# 7_-ADC_Chip.net
KiCad netlist of a schematic drawn in Altium Designer
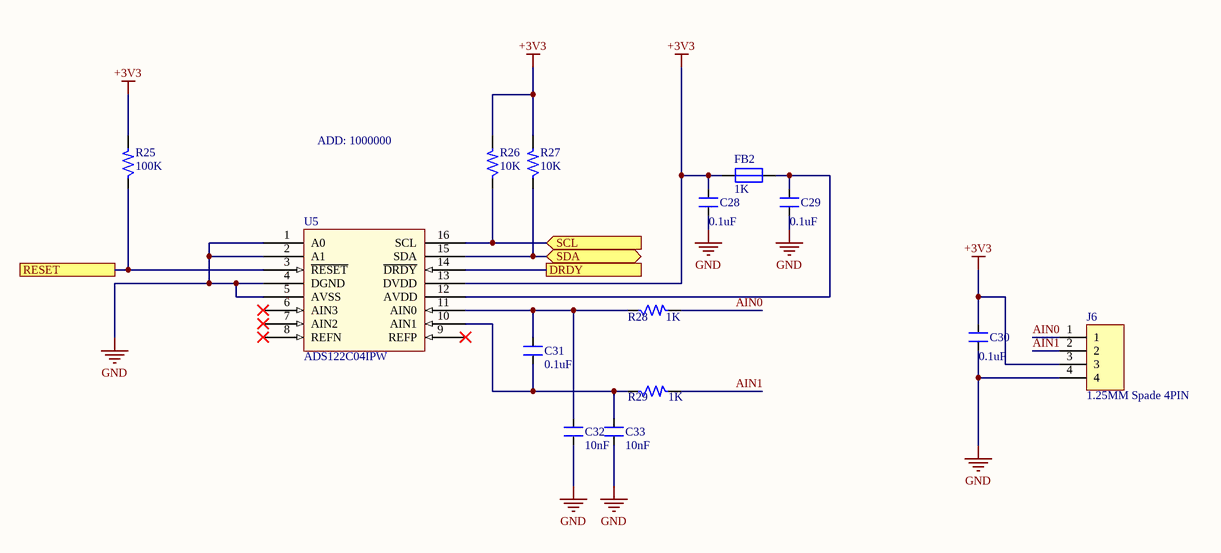
[diagram p0: [7]-ADC Chip.SchDoc]

(export (version "E")
  (design (tool "Eeschema 10.0.6"))
  (components
    (comp (ref "C28")
      (value "0.1uF")
      (footprint "CAP_0805")
      (description "0.1µF ±10% 50V Ceramic Capacitor X7R 0805 (2012 Metric)")
      (fields
        (field (name "MANUFACTURER") "Samsung")
        (field (name "MANUFACTURER PART NUMBER") "CL21B104KBCNNNC")
      )
      (libsource (lib "ESTEEMPCBLIB") (part "CAP_0.1uF-50V-10%-0805"))
    )
    (comp (ref "C29")
      (value "0.1uF")
      (footprint "CAP_0805")
      (description "0.1µF ±10% 50V Ceramic Capacitor X7R 0805 (2012 Metric)")
      (fields
        (field (name "MANUFACTURER") "Samsung")
        (field (name "MANUFACTURER PART NUMBER") "CL21B104KBCNNNC")
      )
      (libsource (lib "ESTEEMPCBLIB") (part "CAP_0.1uF-50V-10%-0805"))
    )
    (comp (ref "C30")
      (value "0.1uF")
      (footprint "CAP_0805")
      (description "0.1µF ±10% 50V Ceramic Capacitor X7R 0805 (2012 Metric)")
      (fields
        (field (name "MANUFACTURER") "Samsung")
        (field (name "MANUFACTURER PART NUMBER") "CL21B104KBCNNNC")
      )
      (libsource (lib "ESTEEMPCBLIB") (part "CAP_0.1uF-50V-10%-0805"))
    )
    (comp (ref "C31")
      (value "0.1uF")
      (footprint "CAP_0805")
      (description "0.1µF ±10% 50V Ceramic Capacitor X7R 0805 (2012 Metric)")
      (fields
        (field (name "MANUFACTURER") "Samsung")
        (field (name "MANUFACTURER PART NUMBER") "CL21B104KBCNNNC")
      )
      (libsource (lib "ESTEEMPCBLIB") (part "CAP_0.1uF-50V-10%-0805"))
    )
    (comp (ref "C32")
      (value "10nF")
      (footprint "CAP_0805")
      (description "10000pF ±10% 50V Ceramic Capacitor X7R 0805 (2012 Metric)")
      (fields
        (field (name "MANUFACTURER") "Samsung")
        (field (name "MANUFACTURER PART NUMBER") "C0805C103K5RECAUTO")
      )
      (libsource (lib "ESTEEMPCBLIB") (part "CAP_10nF-50V-10%-0805"))
    )
    (comp (ref "C33")
      (value "10nF")
      (footprint "CAP_0805")
      (description "10000pF ±10% 50V Ceramic Capacitor X7R 0805 (2012 Metric)")
      (fields
        (field (name "MANUFACTURER") "Samsung")
        (field (name "MANUFACTURER PART NUMBER") "C0805C103K5RECAUTO")
      )
      (libsource (lib "ESTEEMPCBLIB") (part "CAP_10nF-50V-10%-0805"))
    )
    (comp (ref "FB2")
      (value "1K")
      (footprint "IND_0805")
      (description "1 kOhms @ 100MHz 1 Power Line Ferrite Bead 0805 (2012 Metric) 1.6A")
      (fields
        (field (name "MANUFACTURER") "Laird")
        (field (name "MANUFACTURER PART NUMBER") "BLM21SP102SH1D")
      )
      (libsource (lib "ESTEEMPCBLIB") (part "FB_1K-100MHZ-1.6A-0805"))
    )
    (comp (ref "J6")
      (value "1.25MM Spade 4PIN")
      (footprint "CON4_50_653004117322_TH_RA")
      (description "4 Pins, 1 Row 1.25mm Pitch, right angle Connector, male")
      (fields (field (name "MANUFACTURER PART NUMBER") "653004117322") (field (name "MANUFACTURER") "JST"))
      (libsource (lib "ESTEEMPCBLIB") (part "CON-PLG_4X1-50-RA-TH"))
    )
    (comp (ref "R25")
      (value "100K")
      (footprint "RES_0603")
      (description "100 kOhms ±1% 0.1W, 1/10W Chip Resistor 0603 (1608 Metric) Automotive AEC-Q200 Thick Film")
      (fields
        (field (name "MANUFACTURER") "Stackpole Electronics")
        (field (name "MANUFACTURER PART NUMBER") "RMCF0603FT100K")
      )
      (libsource (lib "ESTEEMPCBLIB") (part "RES_100K-0.1W-1%-0603"))
    )
    (comp (ref "R26")
      (value "10K")
      (footprint "RES_0603")
      (description "10 kOhms ±1% 0.1W, 1/10W Chip Resistor 0603 (1608 Metric) Automotive AEC-Q200 Thick Film")
      (fields (field (name "MANUFACTURER") "Walsin") (field (name "MANUFACTURER PART NUMBER") "WR06X1002FTL"))
      (libsource (lib "ESTEEMPCBLIB") (part "RES_10K-0.1W-1%-0603"))
    )
    (comp (ref "R27")
      (value "10K")
      (footprint "RES_0603")
      (description "10 kOhms ±1% 0.1W, 1/10W Chip Resistor 0603 (1608 Metric) Automotive AEC-Q200 Thick Film")
      (fields (field (name "MANUFACTURER") "Walsin") (field (name "MANUFACTURER PART NUMBER") "WR06X1002FTL"))
      (libsource (lib "ESTEEMPCBLIB") (part "RES_10K-0.1W-1%-0603"))
    )
    (comp (ref "R28")
      (value "1K")
      (footprint "RES_0603")
      (description "1 kOhms ±1% 0.1W, 1/10W Chip Resistor 0603 (1608 Metric) Automotive AEC-Q200 Thick Film")
      (fields (field (name "MANUFACTURER") "Walsin") (field (name "MANUFACTURER PART NUMBER") "WR06X1001FTL"))
      (libsource (lib "ESTEEMPCBLIB") (part "RES_1K-0.1W-1%-0603"))
    )
    (comp (ref "R29")
      (value "1K")
      (footprint "RES_0603")
      (description "1 kOhms ±1% 0.1W, 1/10W Chip Resistor 0603 (1608 Metric) Automotive AEC-Q200 Thick Film")
      (fields (field (name "MANUFACTURER") "Walsin") (field (name "MANUFACTURER PART NUMBER") "WR06X1001FTL"))
      (libsource (lib "ESTEEMPCBLIB") (part "RES_1K-0.1W-1%-0603"))
    )
    (comp (ref "U5")
      (value "ADS122C04IPW")
      (footprint "TSSOP16_25-59_294_54X14_SMT")
      (description "24 Bit Analog to Digital Converter 4 Input 1 Sigma-Delta 16-TSSOP")
      (fields (field (name "MANUFACTURER") "Texas Instruments"))
      (libsource (lib "ESTEEMPCBLIB") (part "IC_ADS122C04IPW"))
    )
  )
  (nets
    (net (code "1") (name "+3V3") (class "Default")
      (node (ref "C28") (pin "2") (pinfunction "2_2") (pintype "passive"))
      (node (ref "C30") (pin "2") (pinfunction "2_2") (pintype "passive"))
      (node (ref "FB2") (pin "1") (pinfunction "1_1") (pintype "passive"))
      (node (ref "J6") (pin "3") (pinfunction "3_3") (pintype "passive"))
      (node (ref "R25") (pin "2") (pinfunction "2_2") (pintype "passive"))
      (node (ref "R26") (pin "2") (pinfunction "2_2") (pintype "passive"))
      (node (ref "R27") (pin "2") (pinfunction "2_2") (pintype "passive"))
      (node (ref "U5") (pin "13") (pinfunction "DVDD_13") (pintype "power_in"))
    )
    (net (code "2") (name "/AIN0") (class "Default")
      (node (ref "J6") (pin "1") (pinfunction "1_1") (pintype "passive"))
      (node (ref "R28") (pin "2") (pinfunction "2_2") (pintype "passive"))
    )
    (net (code "3") (name "/AIN1") (class "Default")
      (node (ref "J6") (pin "2") (pinfunction "2_2") (pintype "passive"))
      (node (ref "R29") (pin "2") (pinfunction "2_2") (pintype "passive"))
    )
    (net (code "4") (name "/DRDY") (class "Default")
      (node (ref "U5") (pin "14") (pinfunction "DRDY_14") (pintype "input"))
    )
    (net (code "5") (name "/RESET") (class "Default")
      (node (ref "R25") (pin "1") (pinfunction "1_1") (pintype "passive"))
      (node (ref "U5") (pin "3") (pinfunction "RESET_3") (pintype "input"))
    )
    (net (code "6") (name "/SCL") (class "Default")
      (node (ref "R26") (pin "1") (pinfunction "1_1") (pintype "passive"))
      (node (ref "U5") (pin "16") (pinfunction "SCL_16") (pintype "open_collector"))
    )
    (net (code "7") (name "/SDA") (class "Default")
      (node (ref "R27") (pin "1") (pinfunction "1_1") (pintype "passive"))
      (node (ref "U5") (pin "15") (pinfunction "SDA_15") (pintype "open_collector"))
    )
    (net (code "8") (name "GND") (class "Default")
      (node (ref "C28") (pin "1") (pinfunction "1_1") (pintype "passive"))
      (node (ref "C29") (pin "1") (pinfunction "1_1") (pintype "passive"))
      (node (ref "C30") (pin "1") (pinfunction "1_1") (pintype "passive"))
      (node (ref "C32") (pin "1") (pinfunction "1_1") (pintype "passive"))
      (node (ref "C33") (pin "1") (pinfunction "1_1") (pintype "passive"))
      (node (ref "J6") (pin "4") (pinfunction "4_4") (pintype "passive"))
      (node (ref "U5") (pin "1") (pinfunction "A0_1") (pintype "passive"))
      (node (ref "U5") (pin "2") (pinfunction "A1_2") (pintype "passive"))
      (node (ref "U5") (pin "4") (pinfunction "DGND_4") (pintype "power_in"))
      (node (ref "U5") (pin "5") (pinfunction "AVSS_5") (pintype "power_in"))
    )
    (net (code "9") (name "Net-(U5-AIN0)") (class "Default")
      (node (ref "C31") (pin "2") (pinfunction "2_2") (pintype "passive"))
      (node (ref "C32") (pin "2") (pinfunction "2_2") (pintype "passive"))
      (node (ref "R28") (pin "1") (pinfunction "1_1") (pintype "passive"))
      (node (ref "U5") (pin "11") (pinfunction "AIN0_11") (pintype "input"))
    )
    (net (code "10") (name "Net-(U5-AIN1)") (class "Default")
      (node (ref "C31") (pin "1") (pinfunction "1_1") (pintype "passive"))
      (node (ref "C33") (pin "2") (pinfunction "2_2") (pintype "passive"))
      (node (ref "R29") (pin "1") (pinfunction "1_1") (pintype "passive"))
      (node (ref "U5") (pin "10") (pinfunction "AIN1_10") (pintype "input"))
    )
    (net (code "11") (name "Net-(U5-AVDD)") (class "Default")
      (node (ref "C29") (pin "2") (pinfunction "2_2") (pintype "passive"))
      (node (ref "FB2") (pin "2") (pinfunction "2_2") (pintype "passive"))
      (node (ref "U5") (pin "12") (pinfunction "AVDD_12") (pintype "power_in"))
    )
    (net (code "12") (name "unconnected-(U5-AIN2-Pad7)") (class "Default")
      (node (ref "U5") (pin "7") (pinfunction "AIN2_7") (pintype "input+no_connect"))
    )
    (net (code "13") (name "unconnected-(U5-AIN3-Pad6)") (class "Default")
      (node (ref "U5") (pin "6") (pinfunction "AIN3_6") (pintype "input+no_connect"))
    )
    (net (code "14") (name "unconnected-(U5-REFN-Pad8)") (class "Default")
      (node (ref "U5") (pin "8") (pinfunction "REFN_8") (pintype "input+no_connect"))
    )
    (net (code "15") (name "unconnected-(U5-REFP-Pad9)") (class "Default")
      (node (ref "U5") (pin "9") (pinfunction "REFP_9") (pintype "input+no_connect"))
    )
  )
)
